# Network_L.net
KiCad netlist of a schematic drawn in EAGLE
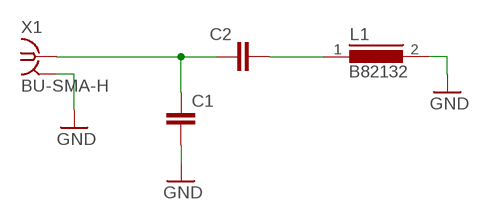
[diagram p0: schematic, sheet 1]

(export (version "E")
  (design (tool "Eeschema 10.0.6"))
  (components
    (comp (ref "C1")
      (value "C-EU075-032X103")
      (footprint "eagle-import:C075-032X103")
      (libsource (lib "eagle-import") (part "C-EU075-032X103"))
    )
    (comp (ref "C2")
      (value "C-EU075-032X103")
      (footprint "eagle-import:C075-032X103")
      (libsource (lib "eagle-import") (part "C-EU075-032X103"))
    )
    (comp (ref "L1")
      (value "B82132")
      (footprint "eagle-import:SUKW2-22")
      (libsource (lib "eagle-import") (part "B82132"))
    )
    (comp (ref "X1")
      (value "BU-SMA-H")
      (footprint "eagle-import:BU-SMA-H")
      (libsource (lib "eagle-import") (part "BU-SMA-H"))
    )
  )
  (nets
    (net (code "1") (name "GND") (class "Default")
      (node (ref "C1") (pin "2") (pinfunction "2_2") (pintype "passive"))
      (node (ref "L1") (pin "2") (pinfunction "2_2") (pintype "passive"))
      (node (ref "X1") (pin "2") (pinfunction "2_2") (pintype "passive"))
      (node (ref "X1") (pin "3") (pinfunction "2_3") (pintype "passive"))
      (node (ref "X1") (pin "4") (pinfunction "2_4") (pintype "passive"))
      (node (ref "X1") (pin "5") (pinfunction "2_5") (pintype "passive"))
    )
    (net (code "2") (name "Net-(C1-Pad1)") (class "Default")
      (node (ref "C1") (pin "1") (pinfunction "1_1") (pintype "passive"))
      (node (ref "C2") (pin "1") (pinfunction "1_1") (pintype "passive"))
      (node (ref "X1") (pin "1") (pinfunction "1_1") (pintype "passive"))
    )
    (net (code "3") (name "Net-(C2-Pad2)") (class "Default")
      (node (ref "C2") (pin "2") (pinfunction "2_2") (pintype "passive"))
      (node (ref "L1") (pin "1") (pinfunction "1_1") (pintype "passive"))
    )
  )
)
